# rev1.net
KiCad netlist of a schematic drawn in Altium Designer
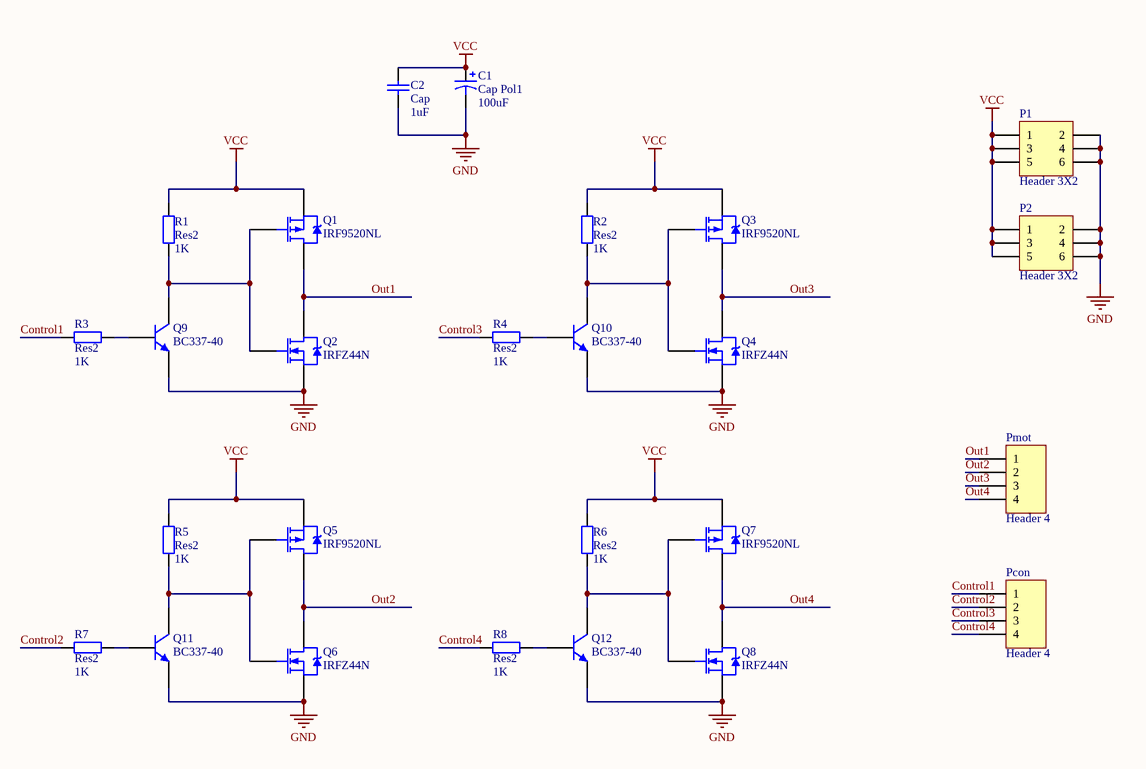
[diagram p0: rev1.SchDoc]

(export (version "E")
  (design (tool "Eeschema 10.0.6"))
  (components
    (comp (ref "C1")
      (value "Cap Pol1")
      (footprint "RB5-10.5")
      (description "Polarized Capacitor (Radial)")
      (fields (field (name "ALTIUM_VALUE") "100uF") (field (name "PUBLISHER") "Altium Limited"))
      (libsource (lib "Miscellaneous Devices") (part "Cap Pol1"))
    )
    (comp (ref "C2")
      (value "Cap")
      (footprint "RAD-0.2")
      (description "Capacitor")
      (fields (field (name "ALTIUM_VALUE") "1uF") (field (name "PUBLISHER") "Altium Limited"))
      (libsource (lib "Miscellaneous Devices") (part "Cap"))
    )
    (comp (ref "P1")
      (value "Header 3X2")
      (footprint "HDR2X3")
      (description "Header, 3-Pin, Dual row")
      (fields (field (name "PUBLISHER") "Altium Limited"))
      (libsource (lib "Miscellaneous Connectors") (part "Header 3X2"))
    )
    (comp (ref "P2")
      (value "Header 3X2")
      (footprint "HDR2X3")
      (description "Header, 3-Pin, Dual row")
      (fields (field (name "PUBLISHER") "Altium Limited"))
      (libsource (lib "Miscellaneous Connectors") (part "Header 3X2"))
    )
    (comp (ref "Pcon")
      (value "Header 4")
      (footprint "HDR1X4")
      (description "Header, 4-Pin")
      (fields (field (name "PUBLISHER") "Altium Limited"))
      (libsource (lib "Miscellaneous Connectors") (part "Header 4"))
    )
    (comp (ref "Pmot")
      (value "Header 4")
      (footprint "HDR1X4")
      (description "Header, 4-Pin")
      (fields (field (name "PUBLISHER") "Altium Limited"))
      (libsource (lib "Miscellaneous Connectors") (part "Header 4"))
    )
    (comp (ref "Q1")
      (value "IRF9520NL")
      (footprint "TO-262")
      (description "HEXFET Power MOSFET")
      (fields (field (name "PUBLISHER") "Altium Limited"))
      (libsource (lib "IR Discrete MOSFET - Power") (part "IRF9520NL"))
    )
    (comp (ref "Q2")
      (value "IRFZ44N")
      (footprint "TO-220AB")
      (description "HEXFET Power MOSFET")
      (fields (field (name "PUBLISHER") "Altium Limited"))
      (libsource (lib "IR Discrete MOSFET - Power") (part "IRFZ44N"))
    )
    (comp (ref "Q3")
      (value "IRF9520NL")
      (footprint "TO-262")
      (description "HEXFET Power MOSFET")
      (fields (field (name "PUBLISHER") "Altium Limited"))
      (libsource (lib "IR Discrete MOSFET - Power") (part "IRF9520NL"))
    )
    (comp (ref "Q4")
      (value "IRFZ44N")
      (footprint "TO-220AB")
      (description "HEXFET Power MOSFET")
      (fields (field (name "PUBLISHER") "Altium Limited"))
      (libsource (lib "IR Discrete MOSFET - Power") (part "IRFZ44N"))
    )
    (comp (ref "Q5")
      (value "IRF9520NL")
      (footprint "TO-262")
      (description "HEXFET Power MOSFET")
      (fields (field (name "PUBLISHER") "Altium Limited"))
      (libsource (lib "IR Discrete MOSFET - Power") (part "IRF9520NL"))
    )
    (comp (ref "Q6")
      (value "IRFZ44N")
      (footprint "TO-220AB")
      (description "HEXFET Power MOSFET")
      (fields (field (name "PUBLISHER") "Altium Limited"))
      (libsource (lib "IR Discrete MOSFET - Power") (part "IRFZ44N"))
    )
    (comp (ref "Q7")
      (value "IRF9520NL")
      (footprint "TO-262")
      (description "HEXFET Power MOSFET")
      (fields (field (name "PUBLISHER") "Altium Limited"))
      (libsource (lib "IR Discrete MOSFET - Power") (part "IRF9520NL"))
    )
    (comp (ref "Q8")
      (value "IRFZ44N")
      (footprint "TO-220AB")
      (description "HEXFET Power MOSFET")
      (fields (field (name "PUBLISHER") "Altium Limited"))
      (libsource (lib "IR Discrete MOSFET - Power") (part "IRFZ44N"))
    )
    (comp (ref "Q9")
      (value "BC337-40")
      (footprint "29-04")
      (description "Amplifier Transistor NPN Silicon")
      (fields (field (name "PUBLISHER") "Altium Limited"))
      (libsource (lib "Motorola Discrete BJT") (part "BC337-40"))
    )
    (comp (ref "Q10")
      (value "BC337-40")
      (footprint "29-04")
      (description "Amplifier Transistor NPN Silicon")
      (fields (field (name "PUBLISHER") "Altium Limited"))
      (libsource (lib "Motorola Discrete BJT") (part "BC337-40"))
    )
    (comp (ref "Q11")
      (value "BC337-40")
      (footprint "29-04")
      (description "Amplifier Transistor NPN Silicon")
      (fields (field (name "PUBLISHER") "Altium Limited"))
      (libsource (lib "Motorola Discrete BJT") (part "BC337-40"))
    )
    (comp (ref "Q12")
      (value "BC337-40")
      (footprint "29-04")
      (description "Amplifier Transistor NPN Silicon")
      (fields (field (name "PUBLISHER") "Altium Limited"))
      (libsource (lib "Motorola Discrete BJT") (part "BC337-40"))
    )
    (comp (ref "R1")
      (value "Res2")
      (footprint "AXIAL-0.4")
      (description "Resistor")
      (fields (field (name "ALTIUM_VALUE") "1K") (field (name "PUBLISHER") "Altium Limited"))
      (libsource (lib "") (part "Res2_1"))
    )
    (comp (ref "R2")
      (value "Res2")
      (footprint "AXIAL-0.4")
      (description "Resistor")
      (fields (field (name "ALTIUM_VALUE") "1K") (field (name "PUBLISHER") "Altium Limited"))
      (libsource (lib "") (part "Res2_1"))
    )
    (comp (ref "R3")
      (value "Res2")
      (footprint "AXIAL-0.4")
      (description "Resistor")
      (fields (field (name "ALTIUM_VALUE") "1K") (field (name "PUBLISHER") "Altium Limited"))
      (libsource (lib "Miscellaneous Devices") (part "Res2"))
    )
    (comp (ref "R4")
      (value "Res2")
      (footprint "AXIAL-0.4")
      (description "Resistor")
      (fields (field (name "ALTIUM_VALUE") "1K") (field (name "PUBLISHER") "Altium Limited"))
      (libsource (lib "Miscellaneous Devices") (part "Res2"))
    )
    (comp (ref "R5")
      (value "Res2")
      (footprint "AXIAL-0.4")
      (description "Resistor")
      (fields (field (name "ALTIUM_VALUE") "1K") (field (name "PUBLISHER") "Altium Limited"))
      (libsource (lib "") (part "Res2_1"))
    )
    (comp (ref "R6")
      (value "Res2")
      (footprint "AXIAL-0.4")
      (description "Resistor")
      (fields (field (name "ALTIUM_VALUE") "1K") (field (name "PUBLISHER") "Altium Limited"))
      (libsource (lib "") (part "Res2_1"))
    )
    (comp (ref "R7")
      (value "Res2")
      (footprint "AXIAL-0.4")
      (description "Resistor")
      (fields (field (name "ALTIUM_VALUE") "1K") (field (name "PUBLISHER") "Altium Limited"))
      (libsource (lib "Miscellaneous Devices") (part "Res2"))
    )
    (comp (ref "R8")
      (value "Res2")
      (footprint "AXIAL-0.4")
      (description "Resistor")
      (fields (field (name "ALTIUM_VALUE") "1K") (field (name "PUBLISHER") "Altium Limited"))
      (libsource (lib "Miscellaneous Devices") (part "Res2"))
    )
  )
  (nets
    (net (code "1") (name "/Control1") (class "Default")
      (node (ref "Pcon") (pin "1") (pinfunction "1_1") (pintype "passive"))
      (node (ref "R3") (pin "2") (pinfunction "2_2") (pintype "passive"))
    )
    (net (code "2") (name "/Control2") (class "Default")
      (node (ref "Pcon") (pin "2") (pinfunction "2_2") (pintype "passive"))
      (node (ref "R7") (pin "2") (pinfunction "2_2") (pintype "passive"))
    )
    (net (code "3") (name "/Control3") (class "Default")
      (node (ref "Pcon") (pin "3") (pinfunction "3_3") (pintype "passive"))
      (node (ref "R4") (pin "2") (pinfunction "2_2") (pintype "passive"))
    )
    (net (code "4") (name "/Control4") (class "Default")
      (node (ref "Pcon") (pin "4") (pinfunction "4_4") (pintype "passive"))
      (node (ref "R8") (pin "2") (pinfunction "2_2") (pintype "passive"))
    )
    (net (code "5") (name "/Out1") (class "Default")
      (node (ref "Pmot") (pin "1") (pinfunction "1_1") (pintype "passive"))
      (node (ref "Q1") (pin "2") (pinfunction "D_2") (pintype "passive"))
      (node (ref "Q2") (pin "2") (pinfunction "D_2") (pintype "passive"))
    )
    (net (code "6") (name "/Out2") (class "Default")
      (node (ref "Pmot") (pin "2") (pinfunction "2_2") (pintype "passive"))
      (node (ref "Q5") (pin "2") (pinfunction "D_2") (pintype "passive"))
      (node (ref "Q6") (pin "2") (pinfunction "D_2") (pintype "passive"))
    )
    (net (code "7") (name "/Out3") (class "Default")
      (node (ref "Pmot") (pin "3") (pinfunction "3_3") (pintype "passive"))
      (node (ref "Q3") (pin "2") (pinfunction "D_2") (pintype "passive"))
      (node (ref "Q4") (pin "2") (pinfunction "D_2") (pintype "passive"))
    )
    (net (code "8") (name "/Out4") (class "Default")
      (node (ref "Pmot") (pin "4") (pinfunction "4_4") (pintype "passive"))
      (node (ref "Q7") (pin "2") (pinfunction "D_2") (pintype "passive"))
      (node (ref "Q8") (pin "2") (pinfunction "D_2") (pintype "passive"))
    )
    (net (code "9") (name "GND") (class "Default")
      (node (ref "C1") (pin "2") (pinfunction "2_2") (pintype "passive"))
      (node (ref "C2") (pin "1") (pinfunction "1_1") (pintype "passive"))
      (node (ref "P1") (pin "2") (pinfunction "2_2") (pintype "passive"))
      (node (ref "P1") (pin "4") (pinfunction "4_4") (pintype "passive"))
      (node (ref "P1") (pin "6") (pinfunction "6_6") (pintype "passive"))
      (node (ref "P2") (pin "2") (pinfunction "2_2") (pintype "passive"))
      (node (ref "P2") (pin "4") (pinfunction "4_4") (pintype "passive"))
      (node (ref "P2") (pin "6") (pinfunction "6_6") (pintype "passive"))
      (node (ref "Q10") (pin "3") (pinfunction "E_3") (pintype "passive"))
      (node (ref "Q11") (pin "3") (pinfunction "E_3") (pintype "passive"))
      (node (ref "Q12") (pin "3") (pinfunction "E_3") (pintype "passive"))
      (node (ref "Q2") (pin "3") (pinfunction "S_3") (pintype "passive"))
      (node (ref "Q4") (pin "3") (pinfunction "S_3") (pintype "passive"))
      (node (ref "Q6") (pin "3") (pinfunction "S_3") (pintype "passive"))
      (node (ref "Q8") (pin "3") (pinfunction "S_3") (pintype "passive"))
      (node (ref "Q9") (pin "3") (pinfunction "E_3") (pintype "passive"))
    )
    (net (code "10") (name "Net-(Q1-G)") (class "Default")
      (node (ref "Q1") (pin "1") (pinfunction "G_1") (pintype "passive"))
      (node (ref "Q2") (pin "1") (pinfunction "G_1") (pintype "passive"))
      (node (ref "Q9") (pin "1") (pinfunction "C_1") (pintype "passive"))
      (node (ref "R1") (pin "1") (pinfunction "1_1") (pintype "passive"))
    )
    (net (code "11") (name "Net-(Q9-B)") (class "Default")
      (node (ref "Q9") (pin "2") (pinfunction "B_2") (pintype "passive"))
      (node (ref "R3") (pin "1") (pinfunction "1_1") (pintype "passive"))
    )
    (net (code "12") (name "Net-(Q10-B)") (class "Default")
      (node (ref "Q10") (pin "2") (pinfunction "B_2") (pintype "passive"))
      (node (ref "R4") (pin "1") (pinfunction "1_1") (pintype "passive"))
    )
    (net (code "13") (name "Net-(Q10-C)") (class "Default")
      (node (ref "Q10") (pin "1") (pinfunction "C_1") (pintype "passive"))
      (node (ref "Q3") (pin "1") (pinfunction "G_1") (pintype "passive"))
      (node (ref "Q4") (pin "1") (pinfunction "G_1") (pintype "passive"))
      (node (ref "R2") (pin "1") (pinfunction "1_1") (pintype "passive"))
    )
    (net (code "14") (name "Net-(Q11-B)") (class "Default")
      (node (ref "Q11") (pin "2") (pinfunction "B_2") (pintype "passive"))
      (node (ref "R7") (pin "1") (pinfunction "1_1") (pintype "passive"))
    )
    (net (code "15") (name "Net-(Q11-C)") (class "Default")
      (node (ref "Q11") (pin "1") (pinfunction "C_1") (pintype "passive"))
      (node (ref "Q5") (pin "1") (pinfunction "G_1") (pintype "passive"))
      (node (ref "Q6") (pin "1") (pinfunction "G_1") (pintype "passive"))
      (node (ref "R5") (pin "1") (pinfunction "1_1") (pintype "passive"))
    )
    (net (code "16") (name "Net-(Q12-B)") (class "Default")
      (node (ref "Q12") (pin "2") (pinfunction "B_2") (pintype "passive"))
      (node (ref "R8") (pin "1") (pinfunction "1_1") (pintype "passive"))
    )
    (net (code "17") (name "Net-(Q12-C)") (class "Default")
      (node (ref "Q12") (pin "1") (pinfunction "C_1") (pintype "passive"))
      (node (ref "Q7") (pin "1") (pinfunction "G_1") (pintype "passive"))
      (node (ref "Q8") (pin "1") (pinfunction "G_1") (pintype "passive"))
      (node (ref "R6") (pin "1") (pinfunction "1_1") (pintype "passive"))
    )
    (net (code "18") (name "VCC") (class "Default")
      (node (ref "C1") (pin "1") (pinfunction "1_1") (pintype "passive"))
      (node (ref "C2") (pin "2") (pinfunction "2_2") (pintype "passive"))
      (node (ref "P1") (pin "1") (pinfunction "1_1") (pintype "passive"))
      (node (ref "P1") (pin "3") (pinfunction "3_3") (pintype "passive"))
      (node (ref "P1") (pin "5") (pinfunction "5_5") (pintype "passive"))
      (node (ref "P2") (pin "1") (pinfunction "1_1") (pintype "passive"))
      (node (ref "P2") (pin "3") (pinfunction "3_3") (pintype "passive"))
      (node (ref "P2") (pin "5") (pinfunction "5_5") (pintype "passive"))
      (node (ref "Q1") (pin "3") (pinfunction "S_3") (pintype "passive"))
      (node (ref "Q3") (pin "3") (pinfunction "S_3") (pintype "passive"))
      (node (ref "Q5") (pin "3") (pinfunction "S_3") (pintype "passive"))
      (node (ref "Q7") (pin "3") (pinfunction "S_3") (pintype "passive"))
      (node (ref "R1") (pin "2") (pinfunction "2_2") (pintype "passive"))
      (node (ref "R2") (pin "2") (pinfunction "2_2") (pintype "passive"))
      (node (ref "R5") (pin "2") (pinfunction "2_2") (pintype "passive"))
      (node (ref "R6") (pin "2") (pinfunction "2_2") (pintype "passive"))
    )
  )
)
